# 464414_22-02_Sheet1.net
KiCad netlist of a schematic drawn in Altium Designer
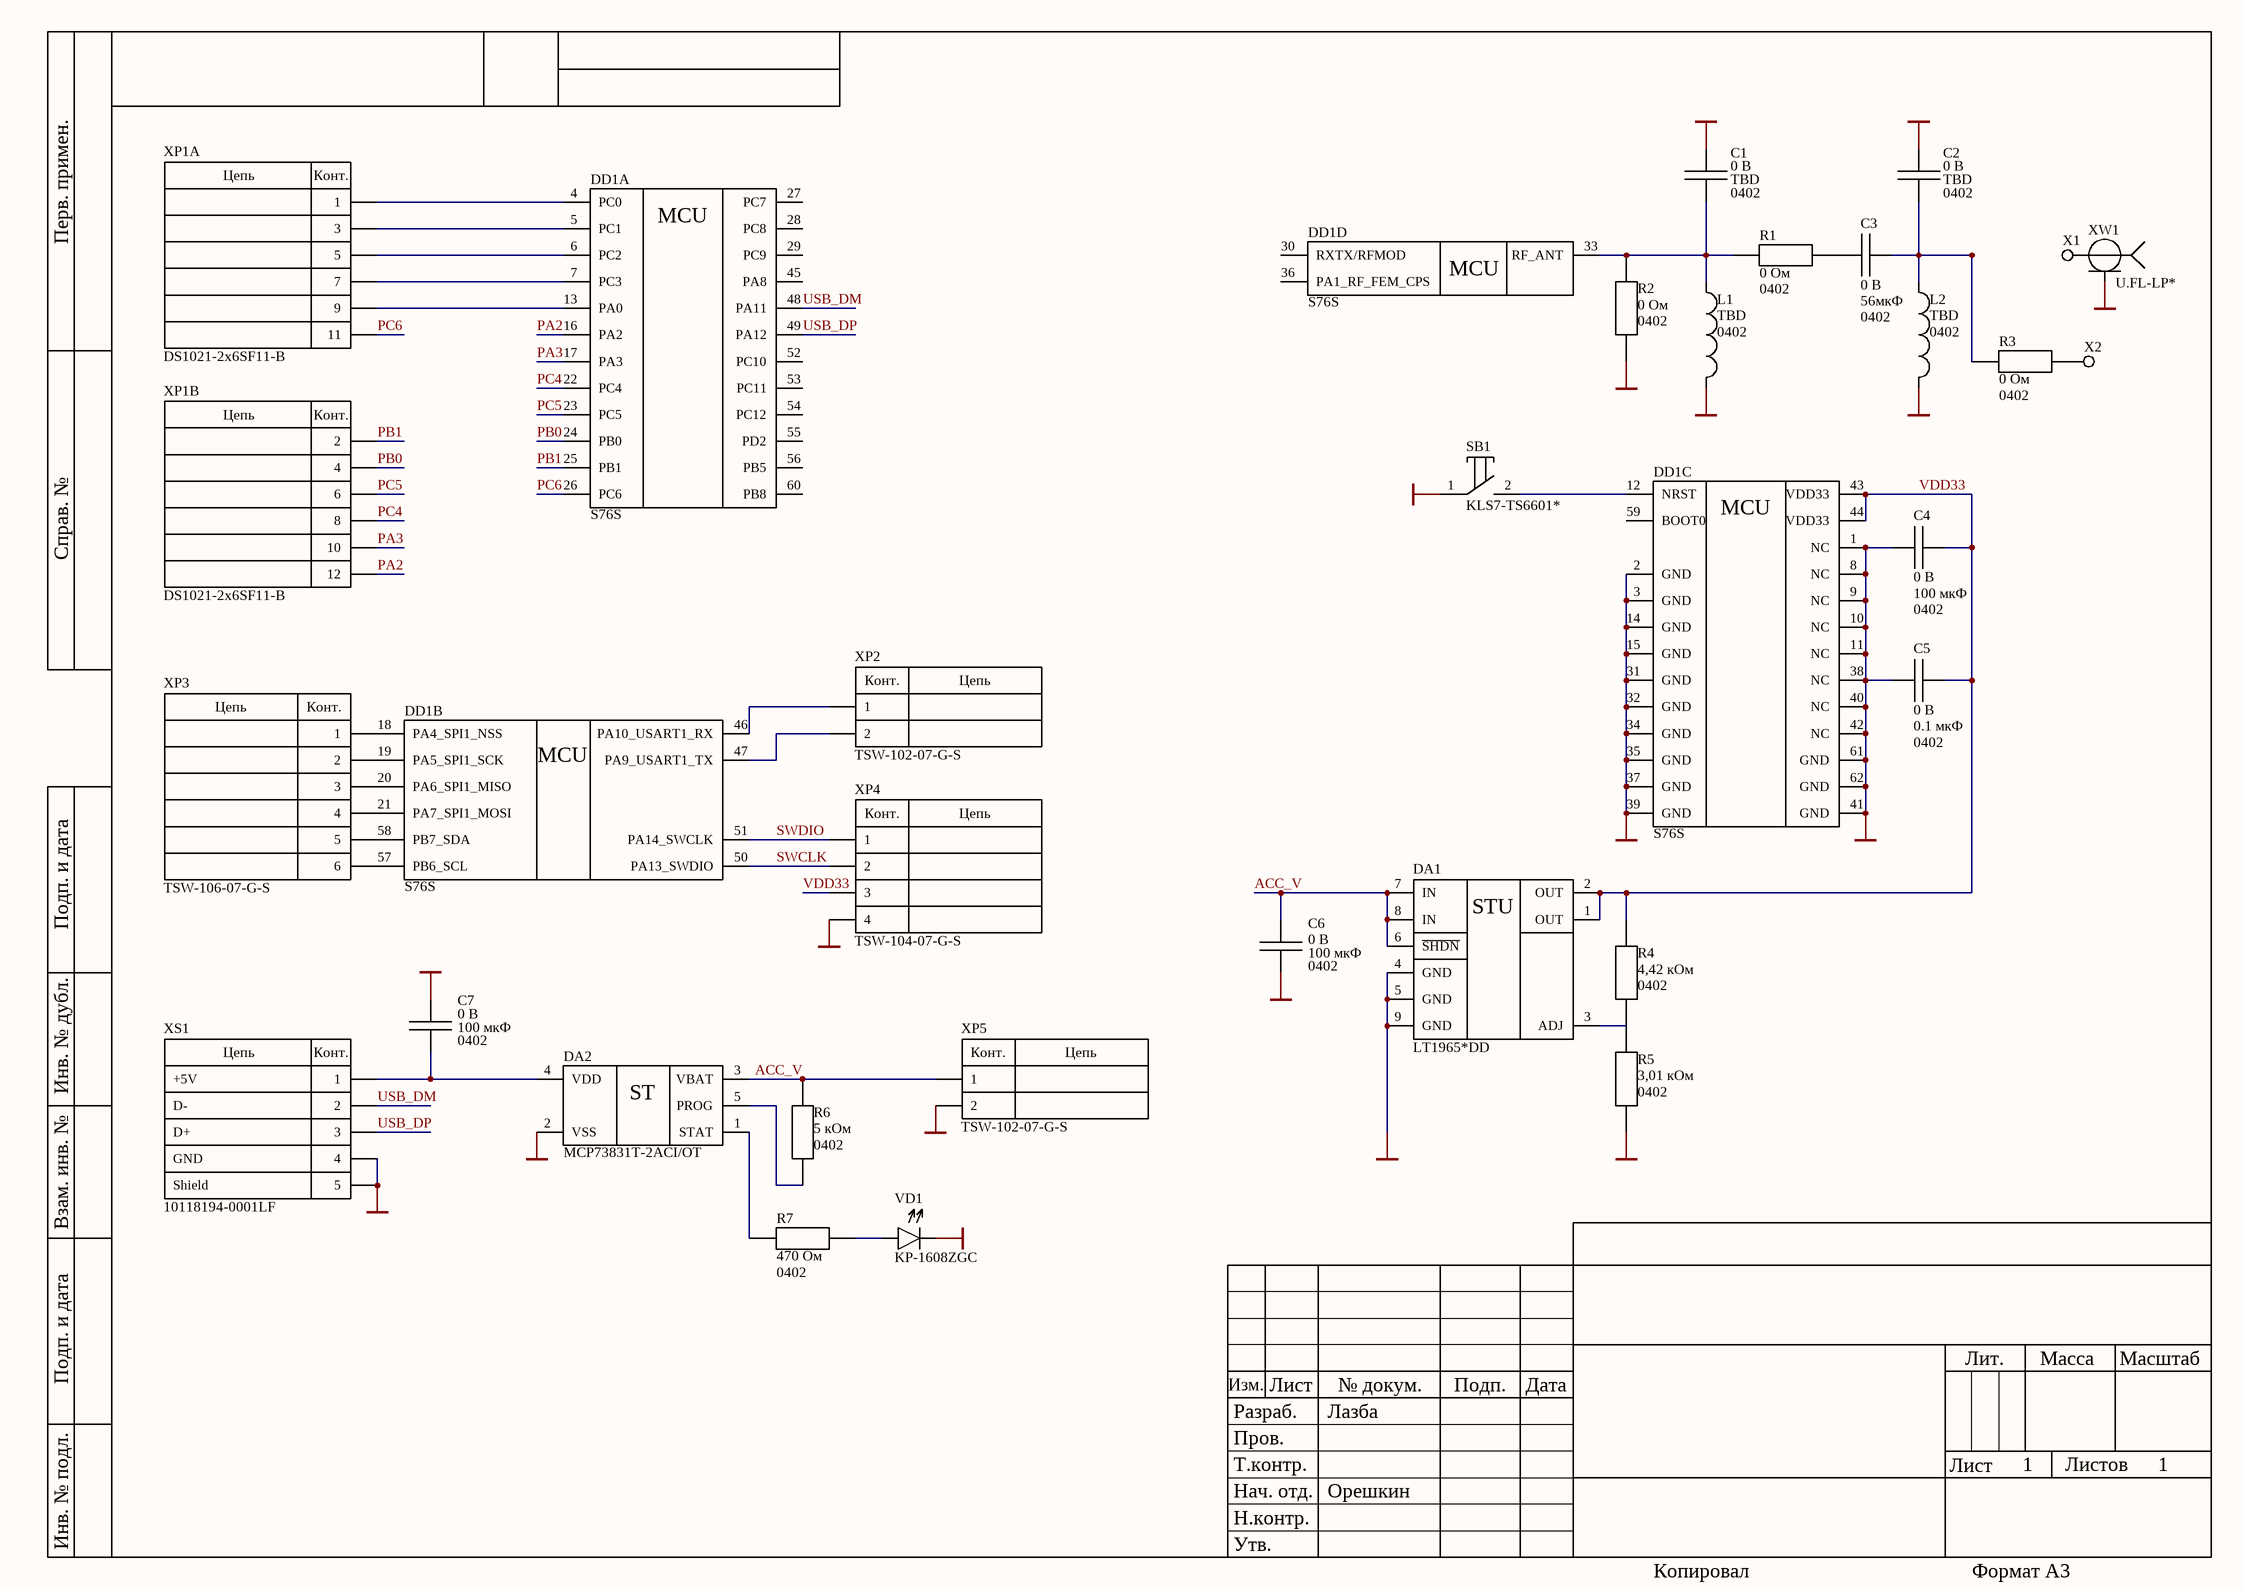
[diagram p0: МПСУ.464414.22-02 Sheet1.SchDoc]

(export (version "E")
  (design (tool "Eeschema 10.0.6"))
  (components
    (comp (ref "C1")
      (value "TBD")
      (footprint "Passive_V2_0:CAPC100X50X55L20N")
      (description "Capacitor 0402")
      (fields
        (field (name "TOLERANCE") "0 %")
        (field (name "PEAK_CONDITION") "0 В")
        (field (name "PACKAGE") "0402")
        (field (name "Comment") "TBD ± 0 % 0 В  0402 ")
        (field (name "DESIGNER") "Свидерский")
      )
      (libsource (lib "Passive_V2_0") (part "C 0402"))
    )
    (comp (ref "C2")
      (value "TBD")
      (footprint "Passive_V2_0:CAPC100X50X55L20N")
      (description "Capacitor 0402")
      (fields
        (field (name "TOLERANCE") "0 %")
        (field (name "PEAK_CONDITION") "0 В")
        (field (name "PACKAGE") "0402")
        (field (name "Comment") "TBD ± 0 % 0 В  0402 ")
        (field (name "DESIGNER") "Свидерский")
      )
      (libsource (lib "Passive_V2_0") (part "C 0402"))
    )
    (comp (ref "C3")
      (value "56мкФ")
      (footprint "Passive_V2_0:CAPC100X50X55L20N")
      (description "Capacitor 0402")
      (fields
        (field (name "TOLERANCE") "0 %")
        (field (name "PEAK_CONDITION") "0 В")
        (field (name "PACKAGE") "0402")
        (field (name "Comment") "56мкФ ± 0 % 0 В  0402 ")
        (field (name "DESIGNER") "Свидерский")
      )
      (libsource (lib "Passive_V2_0") (part "C 0402"))
    )
    (comp (ref "C4")
      (value "100 мкФ")
      (footprint "Passive_V2_0:CAPC100X50X55L20N")
      (description "Capacitor 0402")
      (fields
        (field (name "TOLERANCE") "0 %")
        (field (name "PEAK_CONDITION") "0 В")
        (field (name "PACKAGE") "0402")
        (field (name "Comment") "100 мкФ ± 0 % 0 В  0402 ")
        (field (name "DESIGNER") "Свидерский")
      )
      (libsource (lib "Passive_V2_0") (part "C 0402"))
    )
    (comp (ref "C5")
      (value "0.1 мкФ")
      (footprint "Passive_V2_0:CAPC100X50X55L20N")
      (description "Capacitor 0402")
      (fields
        (field (name "TOLERANCE") "0 %")
        (field (name "PEAK_CONDITION") "0 В")
        (field (name "PACKAGE") "0402")
        (field (name "Comment") "0.1 мкФ ± 0 % 0 В  0402 ")
        (field (name "DESIGNER") "Свидерский")
      )
      (libsource (lib "Passive_V2_0") (part "C 0402"))
    )
    (comp (ref "C6")
      (value "100 мкФ")
      (footprint "Passive_V2_0:CAPC100X50X55L20N")
      (description "Capacitor 0402")
      (fields
        (field (name "TOLERANCE") "0 %")
        (field (name "PEAK_CONDITION") "0 В")
        (field (name "PACKAGE") "0402")
        (field (name "Comment") "100 мкФ ± 0 % 0 В  0402 ")
        (field (name "DESIGNER") "Свидерский")
      )
      (libsource (lib "Passive_V2_0") (part "C 0402"))
    )
    (comp (ref "C7")
      (value "100 мкФ")
      (footprint "Passive_V2_0:CAPC100X50X55L20N")
      (description "Capacitor 0402")
      (fields
        (field (name "TOLERANCE") "0 %")
        (field (name "PEAK_CONDITION") "0 В")
        (field (name "PACKAGE") "0402")
        (field (name "Comment") "100 мкФ ± 0 % 0 В  0402 ")
        (field (name "DESIGNER") "Свидерский")
      )
      (libsource (lib "Passive_V2_0") (part "C 0402"))
    )
    (comp (ref "DA1")
      (value "LT1965*DD")
      (footprint "IC_V2_0:SON9P50_300X300X80L40X25T244X160N")
      (description "1.1A, Low Noise,  Low Dropout Linear Regulator")
      (fields
        (field (name "MANUFACTURER") "Analog Devices")
        (field (name "PARTNUMBER") "LT1965*DD")
        (field (name "DESIGNER") "Свидерский")
      )
      (libsource (lib "IC_V2_0") (part "LT1965*DD"))
    )
    (comp (ref "DA2")
      (value "MCP73831T-2ACI/OT")
      (footprint "IC_V2_0:SOTFL95P270X145-5N")
      (description "Miniature Single-Cell, Fully Integrated Li-Ion,\r\nLi-Polymer Charge Management Controllers")
      (fields
        (field (name "MANUFACTURER") "Microchip")
        (field (name "PARTNUMBER") "MCP73831T-2ACI/OT")
        (field (name "DESIGNER") "Лазба")
      )
      (libsource (lib "IC_V2_0") (part "MCP7383*"))
    )
    (comp (ref "DD1")
      (value "DD1")
      (footprint "IC_V2_0:S7XS")
      (fields
        (field (name "MANUFACTURER") "AcSIP")
        (field (name "PARTNUMBER") "S76S")
        (field (name "DESIGNER") "Лазба")
      )
      (libsource (lib "IC_V2_0") (part "S76S"))
    )
    (comp (ref "L1")
      (value "TBD")
      (footprint "Passive_V2_0:INDC100X50X60L10N")
      (description "Inductor 0402")
      (fields
        (field (name "TOLERANCE") "0 %")
        (field (name "PACKAGE") "0402")
        (field (name "Comment") "TBD ± 0 % 0 А 0402 ")
        (field (name "DESIGNER") "Свидерский")
      )
      (libsource (lib "Passive_V2_0") (part "L 0402"))
    )
    (comp (ref "L2")
      (value "TBD")
      (footprint "Passive_V2_0:INDC100X50X60L10N")
      (description "Inductor 0402")
      (fields
        (field (name "TOLERANCE") "0 %")
        (field (name "PACKAGE") "0402")
        (field (name "Comment") "TBD ± 0 % 0 А 0402 ")
        (field (name "DESIGNER") "Свидерский")
      )
      (libsource (lib "Passive_V2_0") (part "L 0402"))
    )
    (comp (ref "R1")
      (value "0 Ом")
      (footprint "Passive_V2_0:RESC100X50X40L25N")
      (description "Resistor 0402")
      (fields
        (field (name "TOLERANCE") "0 %")
        (field (name "PACKAGE") "0402")
        (field (name "Comment") "0 Ом ± 0 % 0 Вт 0402 ")
        (field (name "DESIGNER") "Свидерский")
      )
      (libsource (lib "") (part "R 0402_1"))
    )
    (comp (ref "R2")
      (value "0 Ом")
      (footprint "Passive_V2_0:RESC100X50X40L25N")
      (description "Resistor 0402")
      (fields
        (field (name "TOLERANCE") "0 %")
        (field (name "PACKAGE") "0402")
        (field (name "Comment") "0 Ом ± 0 % 0 Вт 0402 ")
        (field (name "DESIGNER") "Свидерский")
      )
      (libsource (lib "") (part "R 0402_2"))
    )
    (comp (ref "R3")
      (value "0 Ом")
      (footprint "Passive_V2_0:RESC100X50X40L25N")
      (description "Resistor 0402")
      (fields
        (field (name "TOLERANCE") "0 %")
        (field (name "PACKAGE") "0402")
        (field (name "Comment") "0 Ом ± 0 % 0 Вт 0402 ")
        (field (name "DESIGNER") "Свидерский")
      )
      (libsource (lib "") (part "R 0402_1"))
    )
    (comp (ref "R4")
      (value "4,42 кОм")
      (footprint "Passive_V2_0:RESC100X50X40L25N")
      (description "Resistor 0402")
      (fields
        (field (name "TOLERANCE") "0 %")
        (field (name "PACKAGE") "0402")
        (field (name "Comment") "4,42 кОм ± 0 % 0 Вт 0402 ")
        (field (name "DESIGNER") "Свидерский")
      )
      (libsource (lib "") (part "R 0402_2"))
    )
    (comp (ref "R5")
      (value "3,01 кОм")
      (footprint "Passive_V2_0:RESC100X50X40L25N")
      (description "Resistor 0402")
      (fields
        (field (name "TOLERANCE") "0 %")
        (field (name "PACKAGE") "0402")
        (field (name "Comment") "3,01 кОм ± 0 % 0 Вт 0402 ")
        (field (name "DESIGNER") "Свидерский")
      )
      (libsource (lib "") (part "R 0402_2"))
    )
    (comp (ref "R6")
      (value "5 кОм")
      (footprint "Passive_V2_0:RESC100X50X40L25N")
      (description "Resistor 0402")
      (fields
        (field (name "TOLERANCE") "0 %")
        (field (name "PACKAGE") "0402")
        (field (name "Comment") "5 кОм ± 0 % 0 Вт 0402 ")
        (field (name "DESIGNER") "Свидерский")
      )
      (libsource (lib "Passive_V2_0") (part "R 0402"))
    )
    (comp (ref "R7")
      (value "470 Ом")
      (footprint "Passive_V2_0:RESC100X50X40L25N")
      (description "Resistor 0402")
      (fields
        (field (name "TOLERANCE") "0 %")
        (field (name "PACKAGE") "0402")
        (field (name "Comment") "470 Ом ± 0 % 0 Вт 0402 ")
        (field (name "DESIGNER") "Свидерский")
      )
      (libsource (lib "") (part "R 0402_1"))
    )
    (comp (ref "SB1")
      (value "SB1")
      (footprint "Passive_V2_0:KLS7-TS6601")
      (description "6x6 Tact Switch Series")
      (fields
        (field (name "MANUFACTURER") "KLS electronic co ltd")
        (field (name "PARTNUMBER") "KLS7-TS6601*")
        (field (name "DESIGNER") "Лазба")
      )
      (libsource (lib "Passive_V2_0") (part "KLS7-TS6601*"))
    )
    (comp (ref "VD1")
      (value "KP-1608ZGC")
      (footprint "Discrete_V2_0:KP-1608ZGC")
      (description "1.6X0.8mm SMD CHIP LED LAMP")
      (fields
        (field (name "MANUFACTURER") "Kingbright")
        (field (name "PARTNUMBER") "KP-1608ZGC")
        (field (name "DESIGNER") "Ушакова")
      )
      (libsource (lib "Discrete_V2_0") (part "KP-1608***"))
    )
    (comp (ref "X1")
      (value "Contact Pad")
      (footprint "Primitive_V2_0:Contact_Pad 0.55x0.55")
      (description "Контактная площадка (1,5 х 1,5 мм) для запайки провода")
      (fields (field (name "DESIGNER") "Свидерский"))
      (libsource (lib "Primitive_V2_0") (part "Contact Pad"))
    )
    (comp (ref "X2")
      (value "Contact Pad")
      (footprint "Primitive_V2_0:Contact_Pad 0.55x0.55")
      (description "Контактная площадка (1,5 х 1,5 мм) для запайки провода")
      (fields (field (name "DESIGNER") "Свидерский"))
      (libsource (lib "Primitive_V2_0") (part "Contact Pad"))
    )
    (comp (ref "XP1")
      (value "DS1021-2x6SF11-B")
      (footprint "Connectors_V2_0:HDRV12W64P254_6X2_1524X508H600")
      (description "Вилка 2,54мм")
      (fields
        (field (name "MANUFACTURER") "Connfly Electronic")
        (field (name "PARTNUMBER") "DS1021-2x6SF11-B")
        (field (name "DESIGNER") "Свидерский")
      )
      (libsource (lib "Connectors_V2_0") (part "DS1021-2x6SF11-B"))
    )
    (comp (ref "XP2")
      (value "TSW-102-07-G-S")
      (footprint "Connectors_V2_0:TSW-102-07-G-S")
      (description "2x1 Вилка 2,54 мм")
      (fields
        (field (name "MANUFACTURER") "Samtec")
        (field (name "PARTNUMBER") "TSW-102-07-G-S")
        (field (name "DESIGNER") "Погорельский")
      )
      (libsource (lib "Connectors_V2_0") (part "TSW-102-07-G-S"))
    )
    (comp (ref "XP3")
      (value "TSW-106-07-G-S")
      (footprint "Connectors_V2_0:TSW-106-07-G-S")
      (description "Вилка 2,54 мм")
      (fields
        (field (name "MANUFACTURER") "Samtec")
        (field (name "PARTNUMBER") "TSW-106-07-G-S")
        (field (name "DESIGNER") "Лазба")
      )
      (libsource (lib "Connectors_V2_0") (part "TSW-106-07-G-S"))
    )
    (comp (ref "XP4")
      (value "TSW-104-07-G-S")
      (footprint "Connectors_V2_0:TSW-104-07-G-S")
      (description "Вилка 2,54 мм")
      (fields
        (field (name "MANUFACTURER") "Samtec")
        (field (name "PARTNUMBER") "TSW-104-07-G-S")
        (field (name "DESIGNER") "Затонская")
      )
      (libsource (lib "Connectors_V2_0") (part "TSW-104-07-G-S"))
    )
    (comp (ref "XP5")
      (value "TSW-102-07-G-S")
      (footprint "Connectors_V2_0:TSW-102-07-G-S")
      (description "2x1 Вилка 2,54 мм")
      (fields
        (field (name "MANUFACTURER") "Samtec")
        (field (name "PARTNUMBER") "TSW-102-07-G-S")
        (field (name "DESIGNER") "Погорельский")
      )
      (libsource (lib "Connectors_V2_0") (part "TSW-102-07-G-S"))
    )
    (comp (ref "XS1")
      (value "10118194-0001LF")
      (footprint "Connectors_V2_0:micro_USB_TH")
      (description "micro USB, Through Hole Mount")
      (fields
        (field (name "MANUFACTURER") "Amphenal ICC")
        (field (name "PARTNUMBER") "10118194-0001LF")
        (field (name "DESIGNER") "Свидерский")
      )
      (libsource (lib "Connectors_V2_0") (part "10118194-0001LF"))
    )
    (comp (ref "XW1")
      (value "U.FL-LP*")
      (footprint "Connectors_V2_0:U.FL-LP")
      (description "RF connector, Right Angle Jack PCB SMA Female End Launch Connector")
      (fields
        (field (name "MANUFACTURER") "Hirose Electric")
        (field (name "PARTNUMBER") "U.FL-LP*")
        (field (name "DESIGNER") "Лазба")
      )
      (libsource (lib "Connectors_V2_0") (part "U.FL-R-SMT"))
    )
  )
  (nets
    (net (code "1") (name "/ACC_V") (class "Default")
      (node (ref "C6") (pin "1") (pinfunction "1_1") (pintype "passive"))
      (node (ref "DA1") (pin "6") (pinfunction "~{SHDN}_6") (pintype "passive"))
      (node (ref "DA1") (pin "7") (pinfunction "IN_7") (pintype "passive"))
      (node (ref "DA1") (pin "8") (pinfunction "IN_8") (pintype "passive"))
      (node (ref "DA2") (pin "3") (pinfunction "VBAT_3") (pintype "passive"))
      (node (ref "R6") (pin "2") (pinfunction "2_2") (pintype "passive"))
      (node (ref "XP5") (pin "1") (pinfunction "1_1") (pintype "passive"))
    )
    (net (code "2") (name "/PA2") (class "Default")
      (node (ref "DD1") (pin "16") (pinfunction "PA2_16") (pintype "passive"))
      (node (ref "XP1") (pin "12") (pinfunction "12_12") (pintype "passive"))
    )
    (net (code "3") (name "/PA3") (class "Default")
      (node (ref "DD1") (pin "17") (pinfunction "PA3_17") (pintype "passive"))
      (node (ref "XP1") (pin "10") (pinfunction "10_10") (pintype "passive"))
    )
    (net (code "4") (name "/PB0") (class "Default")
      (node (ref "DD1") (pin "24") (pinfunction "PB0_24") (pintype "passive"))
      (node (ref "XP1") (pin "4") (pinfunction "4_4") (pintype "passive"))
    )
    (net (code "5") (name "/PB1") (class "Default")
      (node (ref "DD1") (pin "25") (pinfunction "PB1_25") (pintype "passive"))
      (node (ref "XP1") (pin "2") (pinfunction "2_2") (pintype "passive"))
    )
    (net (code "6") (name "/PC4") (class "Default")
      (node (ref "DD1") (pin "22") (pinfunction "PC4_22") (pintype "passive"))
      (node (ref "XP1") (pin "8") (pinfunction "8_8") (pintype "passive"))
    )
    (net (code "7") (name "/PC5") (class "Default")
      (node (ref "DD1") (pin "23") (pinfunction "PC5_23") (pintype "passive"))
      (node (ref "XP1") (pin "6") (pinfunction "6_6") (pintype "passive"))
    )
    (net (code "8") (name "/PC6") (class "Default")
      (node (ref "DD1") (pin "26") (pinfunction "PC6_26") (pintype "passive"))
      (node (ref "XP1") (pin "11") (pinfunction "11_11") (pintype "passive"))
    )
    (net (code "9") (name "/SWCLK") (class "Default")
      (node (ref "DD1") (pin "50") (pinfunction "PA13_SWDIO_50") (pintype "passive"))
      (node (ref "XP4") (pin "2") (pinfunction "2_2") (pintype "passive"))
    )
    (net (code "10") (name "/SWDIO") (class "Default")
      (node (ref "DD1") (pin "51") (pinfunction "PA14_SWCLK_51") (pintype "passive"))
      (node (ref "XP4") (pin "1") (pinfunction "1_1") (pintype "passive"))
    )
    (net (code "11") (name "/USB_DM") (class "Default")
      (node (ref "DD1") (pin "48") (pinfunction "PA11_48") (pintype "passive"))
      (node (ref "XS1") (pin "2") (pinfunction "2_2") (pintype "passive"))
    )
    (net (code "12") (name "/USB_DP") (class "Default")
      (node (ref "DD1") (pin "49") (pinfunction "PA12_49") (pintype "passive"))
      (node (ref "XS1") (pin "3") (pinfunction "3_3") (pintype "passive"))
    )
    (net (code "13") (name "/VDD33") (class "Default")
      (node (ref "C4") (pin "2") (pinfunction "2_2") (pintype "passive"))
      (node (ref "C5") (pin "1") (pinfunction "1_1") (pintype "passive"))
      (node (ref "DA1") (pin "1") (pinfunction "OUT_1") (pintype "passive"))
      (node (ref "DA1") (pin "2") (pinfunction "OUT_2") (pintype "passive"))
      (node (ref "DD1") (pin "43") (pinfunction "VDD33_43") (pintype "passive"))
      (node (ref "DD1") (pin "44") (pinfunction "VDD33_44") (pintype "passive"))
      (node (ref "R4") (pin "1") (pinfunction "1_1") (pintype "passive"))
      (node (ref "XP4") (pin "3") (pinfunction "3_3") (pintype "passive"))
    )
    (net (code "14") (name "GND") (class "Default")
      (node (ref "C1") (pin "2") (pinfunction "2_2") (pintype "passive"))
      (node (ref "C2") (pin "2") (pinfunction "2_2") (pintype "passive"))
      (node (ref "C4") (pin "1") (pinfunction "1_1") (pintype "passive"))
      (node (ref "C5") (pin "2") (pinfunction "2_2") (pintype "passive"))
      (node (ref "C6") (pin "2") (pinfunction "2_2") (pintype "passive"))
      (node (ref "C7") (pin "1") (pinfunction "1_1") (pintype "passive"))
      (node (ref "DA1") (pin "4") (pinfunction "GND_4") (pintype "passive"))
      (node (ref "DA1") (pin "5") (pinfunction "GND_5") (pintype "passive"))
      (node (ref "DA1") (pin "9") (pinfunction "GND_9") (pintype "passive"))
      (node (ref "DA2") (pin "2") (pinfunction "VSS_2") (pintype "passive"))
      (node (ref "DD1") (pin "1") (pinfunction "NC_1") (pintype "passive"))
      (node (ref "DD1") (pin "10") (pinfunction "NC_10") (pintype "passive"))
      (node (ref "DD1") (pin "11") (pinfunction "NC_11") (pintype "passive"))
      (node (ref "DD1") (pin "14") (pinfunction "GND_14") (pintype "passive"))
      (node (ref "DD1") (pin "15") (pinfunction "GND_15") (pintype "passive"))
      (node (ref "DD1") (pin "2") (pinfunction "GND_2") (pintype "passive"))
      (node (ref "DD1") (pin "3") (pinfunction "GND_3") (pintype "passive"))
      (node (ref "DD1") (pin "31") (pinfunction "GND_31") (pintype "passive"))
      (node (ref "DD1") (pin "32") (pinfunction "GND_32") (pintype "passive"))
      (node (ref "DD1") (pin "34") (pinfunction "GND_34") (pintype "passive"))
      (node (ref "DD1") (pin "35") (pinfunction "GND_35") (pintype "passive"))
      (node (ref "DD1") (pin "37") (pinfunction "GND_37") (pintype "passive"))
      (node (ref "DD1") (pin "38") (pinfunction "NC_38") (pintype "passive"))
      (node (ref "DD1") (pin "39") (pinfunction "GND_39") (pintype "passive"))
      (node (ref "DD1") (pin "40") (pinfunction "NC_40") (pintype "passive"))
      (node (ref "DD1") (pin "41") (pinfunction "GND_41") (pintype "passive"))
      (node (ref "DD1") (pin "42") (pinfunction "NC_42") (pintype "passive"))
      (node (ref "DD1") (pin "61") (pinfunction "GND_61") (pintype "passive"))
      (node (ref "DD1") (pin "62") (pinfunction "GND_62") (pintype "passive"))
      (node (ref "DD1") (pin "8") (pinfunction "NC_8") (pintype "passive"))
      (node (ref "DD1") (pin "9") (pinfunction "NC_9") (pintype "passive"))
      (node (ref "L1") (pin "2") (pinfunction "2_2") (pintype "passive"))
      (node (ref "L2") (pin "2") (pinfunction "2_2") (pintype "passive"))
      (node (ref "R2") (pin "2") (pinfunction "2_2") (pintype "passive"))
      (node (ref "R5") (pin "2") (pinfunction "2_2") (pintype "passive"))
      (node (ref "SB1") (pin "1") (pintype "passive"))
      (node (ref "VD1") (pin "2") (pinfunction "2_2") (pintype "passive"))
      (node (ref "XP4") (pin "4") (pinfunction "4_4") (pintype "passive"))
      (node (ref "XP5") (pin "2") (pinfunction "2_2") (pintype "passive"))
      (node (ref "XS1") (pin "4") (pinfunction "4_4") (pintype "passive"))
      (node (ref "XS1") (pin "5") (pinfunction "5_5") (pintype "passive"))
      (node (ref "XW1") (pin "2") (pinfunction "GND_2") (pintype "passive"))
    )
    (net (code "15") (name "Net-(C2-Pad1)") (class "Default")
      (node (ref "C2") (pin "1") (pinfunction "1_1") (pintype "passive"))
      (node (ref "C3") (pin "1") (pinfunction "1_1") (pintype "passive"))
      (node (ref "L2") (pin "1") (pinfunction "1_1") (pintype "passive"))
      (node (ref "R3") (pin "1") (pinfunction "1_1") (pintype "passive"))
    )
    (net (code "16") (name "Net-(C3-Pad2)") (class "Default")
      (node (ref "C3") (pin "2") (pinfunction "2_2") (pintype "passive"))
      (node (ref "R1") (pin "2") (pinfunction "2_2") (pintype "passive"))
    )
    (net (code "17") (name "Net-(DA1-ADJ)") (class "Default")
      (node (ref "DA1") (pin "3") (pinfunction "ADJ_3") (pintype "passive"))
      (node (ref "R4") (pin "2") (pinfunction "2_2") (pintype "passive"))
      (node (ref "R5") (pin "1") (pinfunction "1_1") (pintype "passive"))
    )
    (net (code "18") (name "Net-(DA2-PROG)") (class "Default")
      (node (ref "DA2") (pin "5") (pinfunction "PROG_5") (pintype "passive"))
      (node (ref "R6") (pin "1") (pinfunction "1_1") (pintype "passive"))
    )
    (net (code "19") (name "Net-(DA2-STAT)") (class "Default")
      (node (ref "DA2") (pin "1") (pinfunction "STAT_1") (pintype "passive"))
      (node (ref "R7") (pin "1") (pinfunction "1_1") (pintype "passive"))
    )
    (net (code "20") (name "Net-(DA2-VDD)") (class "Default")
      (node (ref "C7") (pin "2") (pinfunction "2_2") (pintype "passive"))
      (node (ref "DA2") (pin "4") (pinfunction "VDD_4") (pintype "passive"))
      (node (ref "XS1") (pin "1") (pinfunction "1_1") (pintype "passive"))
    )
    (net (code "21") (name "Net-(DD1A-PA0)") (class "Default")
      (node (ref "DD1") (pin "13") (pinfunction "PA0_13") (pintype "passive"))
      (node (ref "XP1") (pin "9") (pinfunction "9_9") (pintype "passive"))
    )
    (net (code "22") (name "Net-(DD1A-PC0)") (class "Default")
      (node (ref "DD1") (pin "4") (pinfunction "PC0_4") (pintype "passive"))
      (node (ref "XP1") (pin "1") (pinfunction "1_1") (pintype "passive"))
    )
    (net (code "23") (name "Net-(DD1A-PC1)") (class "Default")
      (node (ref "DD1") (pin "5") (pinfunction "PC1_5") (pintype "passive"))
      (node (ref "XP1") (pin "3") (pinfunction "3_3") (pintype "passive"))
    )
    (net (code "24") (name "Net-(DD1A-PC2)") (class "Default")
      (node (ref "DD1") (pin "6") (pinfunction "PC2_6") (pintype "passive"))
      (node (ref "XP1") (pin "5") (pinfunction "5_5") (pintype "passive"))
    )
    (net (code "25") (name "Net-(DD1A-PC3)") (class "Default")
      (node (ref "DD1") (pin "7") (pinfunction "PC3_7") (pintype "passive"))
      (node (ref "XP1") (pin "7") (pinfunction "7_7") (pintype "passive"))
    )
    (net (code "26") (name "Net-(DD1B-PA4_SPI1_NSS)") (class "Default")
      (node (ref "DD1") (pin "18") (pinfunction "PA4_SPI1_NSS_18") (pintype "passive"))
      (node (ref "XP3") (pin "1") (pinfunction "1_1") (pintype "passive"))
    )
    (net (code "27") (name "Net-(DD1B-PA5_SPI1_SCK)") (class "Default")
      (node (ref "DD1") (pin "19") (pinfunction "PA5_SPI1_SCK_19") (pintype "passive"))
      (node (ref "XP3") (pin "2") (pinfunction "2_2") (pintype "passive"))
    )
    (net (code "28") (name "Net-(DD1B-PA6_SPI1_MISO)") (class "Default")
      (node (ref "DD1") (pin "20") (pinfunction "PA6_SPI1_MISO_20") (pintype "passive"))
      (node (ref "XP3") (pin "3") (pinfunction "3_3") (pintype "passive"))
    )
    (net (code "29") (name "Net-(DD1B-PA7_SPI1_MOSI)") (class "Default")
      (node (ref "DD1") (pin "21") (pinfunction "PA7_SPI1_MOSI_21") (pintype "passive"))
      (node (ref "XP3") (pin "4") (pinfunction "4_4") (pintype "passive"))
    )
    (net (code "30") (name "Net-(DD1B-PA9_USART1_TX)") (class "Default")
      (node (ref "DD1") (pin "47") (pinfunction "PA9_USART1_TX_47") (pintype "passive"))
      (node (ref "XP2") (pin "2") (pinfunction "2_2") (pintype "passive"))
    )
    (net (code "31") (name "Net-(DD1B-PA10_USART1_RX)") (class "Default")
      (node (ref "DD1") (pin "46") (pinfunction "PA10_USART1_RX_46") (pintype "passive"))
      (node (ref "XP2") (pin "1") (pinfunction "1_1") (pintype "passive"))
    )
    (net (code "32") (name "Net-(DD1B-PB6_SCL)") (class "Default")
      (node (ref "DD1") (pin "57") (pinfunction "PB6_SCL_57") (pintype "passive"))
      (node (ref "XP3") (pin "6") (pinfunction "6_6") (pintype "passive"))
    )
    (net (code "33") (name "Net-(DD1B-PB7_SDA)") (class "Default")
      (node (ref "DD1") (pin "58") (pinfunction "PB7_SDA_58") (pintype "passive"))
      (node (ref "XP3") (pin "5") (pinfunction "5_5") (pintype "passive"))
    )
    (net (code "34") (name "Net-(DD1C-NRST)") (class "Default")
      (node (ref "DD1") (pin "12") (pinfunction "NRST_12") (pintype "passive"))
      (node (ref "SB1") (pin "2") (pintype "passive"))
    )
    (net (code "35") (name "Net-(DD1D-RF_ANT)") (class "Default")
      (node (ref "C1") (pin "1") (pinfunction "1_1") (pintype "passive"))
      (node (ref "DD1") (pin "33") (pinfunction "RF_ANT_33") (pintype "passive"))
      (node (ref "L1") (pin "1") (pinfunction "1_1") (pintype "passive"))
      (node (ref "R1") (pin "1") (pinfunction "1_1") (pintype "passive"))
      (node (ref "R2") (pin "1") (pinfunction "1_1") (pintype "passive"))
    )
    (net (code "36") (name "Net-(R7-Pad2)") (class "Default")
      (node (ref "R7") (pin "2") (pinfunction "2_2") (pintype "passive"))
      (node (ref "VD1") (pin "1") (pinfunction "1_1") (pintype "passive"))
    )
    (net (code "37") (name "Net-(X1-TestPoint)") (class "Default")
      (node (ref "X1") (pin "1") (pinfunction "TestPoint_1") (pintype "passive"))
      (node (ref "XW1") (pin "1") (pinfunction "RF_1") (pintype "passive"))
    )
    (net (code "38") (name "Net-(X2-TestPoint)") (class "Default")
      (node (ref "R3") (pin "2") (pinfunction "2_2") (pintype "passive"))
      (node (ref "X2") (pin "1") (pinfunction "TestPoint_1") (pintype "passive"))
    )
    (net (code "39") (name "unconnected-(DD1A-PA8-Pad45)") (class "Default")
      (node (ref "DD1") (pin "45") (pinfunction "PA8_45") (pintype "passive"))
    )
    (net (code "40") (name "unconnected-(DD1A-PB5-Pad56)") (class "Default")
      (node (ref "DD1") (pin "56") (pinfunction "PB5_56") (pintype "passive"))
    )
    (net (code "41") (name "unconnected-(DD1A-PB8-Pad60)") (class "Default")
      (node (ref "DD1") (pin "60") (pinfunction "PB8_60") (pintype "passive"))
    )
    (net (code "42") (name "unconnected-(DD1A-PC7-Pad27)") (class "Default")
      (node (ref "DD1") (pin "27") (pinfunction "PC7_27") (pintype "passive"))
    )
    (net (code "43") (name "unconnected-(DD1A-PC8-Pad28)") (class "Default")
      (node (ref "DD1") (pin "28") (pinfunction "PC8_28") (pintype "passive"))
    )
    (net (code "44") (name "unconnected-(DD1A-PC9-Pad29)") (class "Default")
      (node (ref "DD1") (pin "29") (pinfunction "PC9_29") (pintype "passive"))
    )
    (net (code "45") (name "unconnected-(DD1A-PC10-Pad52)") (class "Default")
      (node (ref "DD1") (pin "52") (pinfunction "PC10_52") (pintype "passive"))
    )
    (net (code "46") (name "unconnected-(DD1A-PC11-Pad53)") (class "Default")
      (node (ref "DD1") (pin "53") (pinfunction "PC11_53") (pintype "passive"))
    )
    (net (code "47") (name "unconnected-(DD1A-PC12-Pad54)") (class "Default")
      (node (ref "DD1") (pin "54") (pinfunction "PC12_54") (pintype "passive"))
    )
    (net (code "48") (name "unconnected-(DD1A-PD2-Pad55)") (class "Default")
      (node (ref "DD1") (pin "55") (pinfunction "PD2_55") (pintype "passive"))
    )
    (net (code "49") (name "unconnected-(DD1C-BOOT0-Pad59)") (class "Default")
      (node (ref "DD1") (pin "59") (pinfunction "BOOT0_59") (pintype "passive"))
    )
    (net (code "50") (name "unconnected-(DD1D-PA1_RF_FEM_CPS-Pad36)") (class "Default")
      (node (ref "DD1") (pin "36") (pinfunction "PA1_RF_FEM_CPS_36") (pintype "passive"))
    )
    (net (code "51") (name "unconnected-(DD1D-RXTX{slash}RFMOD-Pad30)") (class "Default")
      (node (ref "DD1") (pin "30") (pinfunction "RXTX/RFMOD_30") (pintype "passive"))
    )
  )
)
